# CPU_DDR2.net
KiCad netlist of a schematic drawn in Altium Designer
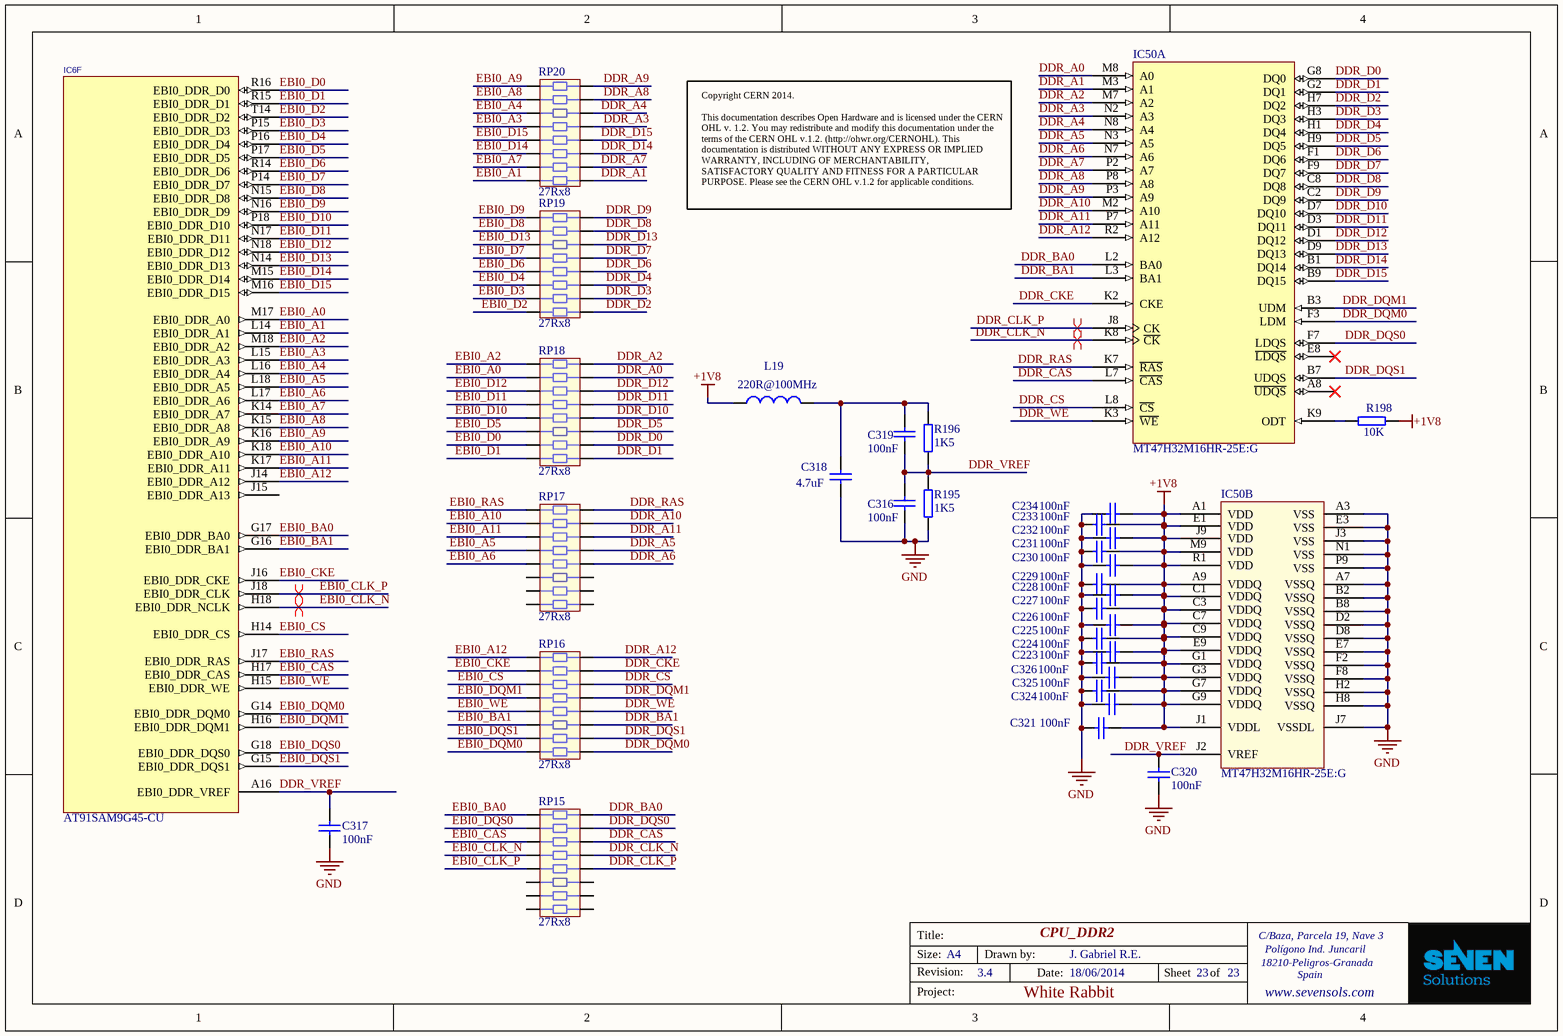
[diagram p0: CPU_DDR2.SchDoc]

(export (version "E")
  (design (tool "Eeschema 10.0.6"))
  (components
    (comp (ref "C223")
      (value "100nF")
      (footprint "CC1005-0402")
      (description "Capacitor")
      (fields
        (field (name "TOLERANCE") "±10%")
        (field (name "VOLTAGE") "16V")
        (field (name "PUBLISHER") "Altium Limited")
      )
      (libsource (lib "wr_switch") (part "Cap"))
    )
    (comp (ref "C224")
      (value "100nF")
      (footprint "CC1005-0402")
      (description "Capacitor")
      (fields
        (field (name "TOLERANCE") "±10%")
        (field (name "VOLTAGE") "16V")
        (field (name "PUBLISHER") "Altium Limited")
      )
      (libsource (lib "wr_switch") (part "Cap"))
    )
    (comp (ref "C225")
      (value "100nF")
      (footprint "CC1005-0402")
      (description "Capacitor")
      (fields
        (field (name "TOLERANCE") "±10%")
        (field (name "VOLTAGE") "16V")
        (field (name "PUBLISHER") "Altium Limited")
      )
      (libsource (lib "wr_switch") (part "Cap"))
    )
    (comp (ref "C226")
      (value "100nF")
      (footprint "CC1005-0402")
      (description "Capacitor")
      (fields
        (field (name "TOLERANCE") "±10%")
        (field (name "VOLTAGE") "16V")
        (field (name "PUBLISHER") "Altium Limited")
      )
      (libsource (lib "wr_switch") (part "Cap"))
    )
    (comp (ref "C227")
      (value "100nF")
      (footprint "CC1005-0402")
      (description "Capacitor")
      (fields
        (field (name "TOLERANCE") "±10%")
        (field (name "VOLTAGE") "16V")
        (field (name "PUBLISHER") "Altium Limited")
      )
      (libsource (lib "wr_switch") (part "Cap"))
    )
    (comp (ref "C228")
      (value "100nF")
      (footprint "CC1005-0402")
      (description "Capacitor")
      (fields
        (field (name "TOLERANCE") "±10%")
        (field (name "VOLTAGE") "16V")
        (field (name "PUBLISHER") "Altium Limited")
      )
      (libsource (lib "wr_switch") (part "Cap"))
    )
    (comp (ref "C229")
      (value "100nF")
      (footprint "CC1005-0402")
      (description "Capacitor")
      (fields
        (field (name "TOLERANCE") "±10%")
        (field (name "VOLTAGE") "16V")
        (field (name "PUBLISHER") "Altium Limited")
      )
      (libsource (lib "wr_switch") (part "Cap"))
    )
    (comp (ref "C230")
      (value "100nF")
      (footprint "CC1005-0402")
      (description "Capacitor")
      (fields
        (field (name "TOLERANCE") "±10%")
        (field (name "VOLTAGE") "16V")
        (field (name "PUBLISHER") "Altium Limited")
      )
      (libsource (lib "wr_switch") (part "Cap"))
    )
    (comp (ref "C231")
      (value "100nF")
      (footprint "CC1005-0402")
      (description "Capacitor")
      (fields
        (field (name "TOLERANCE") "±10%")
        (field (name "VOLTAGE") "16V")
        (field (name "PUBLISHER") "Altium Limited")
      )
      (libsource (lib "wr_switch") (part "Cap"))
    )
    (comp (ref "C232")
      (value "100nF")
      (footprint "CC1005-0402")
      (description "Capacitor")
      (fields
        (field (name "TOLERANCE") "±10%")
        (field (name "VOLTAGE") "16V")
        (field (name "PUBLISHER") "Altium Limited")
      )
      (libsource (lib "wr_switch") (part "Cap"))
    )
    (comp (ref "C233")
      (value "100nF")
      (footprint "CC1005-0402")
      (description "Capacitor")
      (fields
        (field (name "TOLERANCE") "±10%")
        (field (name "VOLTAGE") "16V")
        (field (name "PUBLISHER") "Altium Limited")
      )
      (libsource (lib "wr_switch") (part "Cap"))
    )
    (comp (ref "C234")
      (value "100nF")
      (footprint "CC1005-0402")
      (description "Capacitor")
      (fields
        (field (name "TOLERANCE") "±10%")
        (field (name "VOLTAGE") "16V")
        (field (name "PUBLISHER") "Altium Limited")
      )
      (libsource (lib "wr_switch") (part "Cap"))
    )
    (comp (ref "C316")
      (value "100nF")
      (footprint "CC1005-0402")
      (description "Capacitor")
      (fields
        (field (name "TOLERANCE") "±10%")
        (field (name "VOLTAGE") "16V")
        (field (name "PUBLISHER") "Altium Limited")
      )
      (libsource (lib "wr_switch") (part "Cap"))
    )
    (comp (ref "C317")
      (value "100nF")
      (footprint "CC1005-0402")
      (description "Capacitor")
      (fields
        (field (name "TOLERANCE") "±10%")
        (field (name "VOLTAGE") "16V")
        (field (name "PUBLISHER") "Altium Limited")
      )
      (libsource (lib "wr_switch") (part "Cap"))
    )
    (comp (ref "C318")
      (value "4.7uF")
      (footprint "CC1608-0603")
      (description "Capacitor")
      (fields
        (field (name "TOLERANCE") "±10%")
        (field (name "VOLTAGE") "10V")
        (field (name "PUBLISHER") "Altium Limited")
      )
      (libsource (lib "wr_switch") (part "Cap"))
    )
    (comp (ref "C319")
      (value "100nF")
      (footprint "CC1005-0402")
      (description "Capacitor")
      (fields
        (field (name "TOLERANCE") "±10%")
        (field (name "VOLTAGE") "16V")
        (field (name "PUBLISHER") "Altium Limited")
      )
      (libsource (lib "wr_switch") (part "Cap"))
    )
    (comp (ref "C320")
      (value "100nF")
      (footprint "CC1005-0402")
      (description "Capacitor")
      (fields
        (field (name "TOLERANCE") "±10%")
        (field (name "VOLTAGE") "16V")
        (field (name "PUBLISHER") "Altium Limited")
      )
      (libsource (lib "wr_switch") (part "Cap"))
    )
    (comp (ref "C321")
      (value "100nF")
      (footprint "CC1005-0402")
      (description "Capacitor")
      (fields
        (field (name "TOLERANCE") "±10%")
        (field (name "VOLTAGE") "16V")
        (field (name "PUBLISHER") "Altium Limited")
      )
      (libsource (lib "wr_switch") (part "Cap"))
    )
    (comp (ref "C324")
      (value "100nF")
      (footprint "CC1005-0402")
      (description "Capacitor")
      (fields
        (field (name "TOLERANCE") "±10%")
        (field (name "VOLTAGE") "16V")
        (field (name "PUBLISHER") "Altium Limited")
      )
      (libsource (lib "wr_switch") (part "Cap"))
    )
    (comp (ref "C325")
      (value "100nF")
      (footprint "CC1005-0402")
      (description "Capacitor")
      (fields
        (field (name "TOLERANCE") "±10%")
        (field (name "VOLTAGE") "16V")
        (field (name "PUBLISHER") "Altium Limited")
      )
      (libsource (lib "wr_switch") (part "Cap"))
    )
    (comp (ref "C326")
      (value "100nF")
      (footprint "CC1005-0402")
      (description "Capacitor")
      (fields
        (field (name "TOLERANCE") "±10%")
        (field (name "VOLTAGE") "16V")
        (field (name "PUBLISHER") "Altium Limited")
      )
      (libsource (lib "wr_switch") (part "Cap"))
    )
    (comp (ref "IC6")
      (value "AT91SAM9G45-CU")
      (footprint "TFBGA324")
      (description "Atmel 400MHz ARM926 MCU")
      (libsource (lib "wr_switch") (part "AT91SAM9G45-CU"))
    )
    (comp (ref "IC50")
      (value "MT47H32M16HR-25E:G")
      (footprint "7S_WR:BGA90C80P9X15_1250X800X120")
      (description "DDR2 SDRAM 8Mx16x4 Banks")
      (libsource (lib "wr_switch") (part "MT47H32M16"))
    )
    (comp (ref "L19")
      (value "220R@100MHz Ferrite Bead")
      (footprint "0603")
      (description "ferrite bead")
      (fields (field (name "IMPEDANCE") "220R@100MHz"))
      (libsource (lib "wr_switch") (part "L_FERRITE_BEAD"))
    )
    (comp (ref "R195")
      (value "1K5")
      (footprint "0402")
      (description "SMD Resistor")
      (fields (field (name "TOLERANCE") "±1%"))
      (libsource (lib "wr_switch") (part "RES_SMD"))
    )
    (comp (ref "R196")
      (value "1K5")
      (footprint "0402")
      (description "SMD Resistor")
      (fields (field (name "TOLERANCE") "±1%"))
      (libsource (lib "wr_switch") (part "RES_SMD"))
    )
    (comp (ref "R198")
      (value "10K")
      (footprint "0402")
      (description "SMD Resistor")
      (fields (field (name "TOLERANCE") "±1%"))
      (libsource (lib "wr_switch") (part "RES_SMD"))
    )
    (comp (ref "RP15")
      (value "27Rx8")
      (footprint "RESCAXS50P160X380X60-16N")
      (description "27R, 62.5mW Chip Resistor 8 Elements Array")
      (fields (field (name "TOLERANCE") "±5%") (field (name "Comment") "27R x 8"))
      (libsource (lib "") (part "RES_8xARRAY_1"))
    )
    (comp (ref "RP16")
      (value "27Rx8")
      (footprint "RESCAXS50P160X380X60-16N")
      (description "27R, 62.5mW Chip Resistor 8 Elements Array")
      (fields (field (name "TOLERANCE") "±5%") (field (name "Comment") "27R x 8"))
      (libsource (lib "") (part "RES_8xARRAY_1"))
    )
    (comp (ref "RP17")
      (value "27Rx8")
      (footprint "RESCAXS50P160X380X60-16N")
      (description "27R, 62.5mW Chip Resistor 8 Elements Array")
      (fields (field (name "TOLERANCE") "±5%") (field (name "Comment") "27R x 8"))
      (libsource (lib "") (part "RES_8xARRAY_1"))
    )
    (comp (ref "RP18")
      (value "27Rx8")
      (footprint "RESCAXS50P160X380X60-16N")
      (description "27R, 62.5mW Chip Resistor 8 Elements Array")
      (fields (field (name "TOLERANCE") "±5%") (field (name "Comment") "27R x 8"))
      (libsource (lib "") (part "RES_8xARRAY_1"))
    )
    (comp (ref "RP19")
      (value "27Rx8")
      (footprint "RESCAXS50P160X380X60-16N")
      (description "27R, 62.5mW Chip Resistor 8 Elements Array")
      (fields (field (name "TOLERANCE") "±5%") (field (name "Comment") "27R x 8"))
      (libsource (lib "wr_switch") (part "RES_8xARRAY"))
    )
    (comp (ref "RP20")
      (value "27Rx8")
      (footprint "RESCAXS50P160X380X60-16N")
      (description "27R, 62.5mW Chip Resistor 8 Elements Array")
      (fields (field (name "TOLERANCE") "±5%") (field (name "Comment") "27R x 8"))
      (libsource (lib "wr_switch") (part "RES_8xARRAY"))
    )
  )
  (nets
    (net (code "1") (name "+1V8") (class "Default")
      (node (ref "C223") (pin "1") (pinfunction "1_1") (pintype "passive"))
      (node (ref "C224") (pin "1") (pinfunction "1_1") (pintype "passive"))
      (node (ref "C225") (pin "1") (pinfunction "1_1") (pintype "passive"))
      (node (ref "C226") (pin "1") (pinfunction "1_1") (pintype "passive"))
      (node (ref "C227") (pin "1") (pinfunction "1_1") (pintype "passive"))
      (node (ref "C228") (pin "1") (pinfunction "1_1") (pintype "passive"))
      (node (ref "C229") (pin "1") (pinfunction "1_1") (pintype "passive"))
      (node (ref "C230") (pin "1") (pinfunction "1_1") (pintype "passive"))
      (node (ref "C231") (pin "1") (pinfunction "1_1") (pintype "passive"))
      (node (ref "C232") (pin "1") (pinfunction "1_1") (pintype "passive"))
      (node (ref "C233") (pin "1") (pinfunction "1_1") (pintype "passive"))
      (node (ref "C234") (pin "1") (pinfunction "1_1") (pintype "passive"))
      (node (ref "C321") (pin "1") (pinfunction "1_1") (pintype "passive"))
      (node (ref "C324") (pin "1") (pinfunction "1_1") (pintype "passive"))
      (node (ref "C325") (pin "1") (pinfunction "1_1") (pintype "passive"))
      (node (ref "C326") (pin "1") (pinfunction "1_1") (pintype "passive"))
      (node (ref "IC50") (pin "A1") (pinfunction "VDD_A1") (pintype "power_in"))
      (node (ref "IC50") (pin "A9") (pinfunction "VDDQ_A9") (pintype "power_in"))
      (node (ref "IC50") (pin "C1") (pinfunction "VDDQ_C1") (pintype "power_in"))
      (node (ref "IC50") (pin "C3") (pinfunction "VDDQ_C3") (pintype "power_in"))
      (node (ref "IC50") (pin "C7") (pinfunction "VDDQ_C7") (pintype "power_in"))
      (node (ref "IC50") (pin "C9") (pinfunction "VDDQ_C9") (pintype "power_in"))
      (node (ref "IC50") (pin "E1") (pinfunction "VDD_E1") (pintype "power_in"))
      (node (ref "IC50") (pin "E9") (pinfunction "VDDQ_E9") (pintype "power_in"))
      (node (ref "IC50") (pin "G1") (pinfunction "VDDQ_G1") (pintype "power_in"))
      (node (ref "IC50") (pin "G3") (pinfunction "VDDQ_G3") (pintype "power_in"))
      (node (ref "IC50") (pin "G7") (pinfunction "VDDQ_G7") (pintype "power_in"))
      (node (ref "IC50") (pin "G9") (pinfunction "VDDQ_G9") (pintype "power_in"))
      (node (ref "IC50") (pin "J1") (pinfunction "VDDL_J1") (pintype "power_in"))
      (node (ref "IC50") (pin "J9") (pinfunction "VDD_J9") (pintype "power_in"))
      (node (ref "IC50") (pin "M9") (pinfunction "VDD_M9") (pintype "power_in"))
      (node (ref "IC50") (pin "R1") (pinfunction "VDD_R1") (pintype "power_in"))
      (node (ref "L19") (pin "1") (pinfunction "1_1") (pintype "passive"))
      (node (ref "R198") (pin "1") (pinfunction "1_1") (pintype "passive"))
    )
    (net (code "2") (name "/DDR_A0") (class "Default")
      (node (ref "IC50") (pin "M8") (pinfunction "A0_M8") (pintype "input"))
      (node (ref "RP18") (pin "15") (pinfunction "15_15") (pintype "passive"))
    )
    (net (code "3") (name "/DDR_A1") (class "Default")
      (node (ref "IC50") (pin "M3") (pinfunction "A1_M3") (pintype "input"))
      (node (ref "RP20") (pin "16") (pinfunction "16_16") (pintype "passive"))
    )
    (net (code "4") (name "/DDR_A2") (class "Default")
      (node (ref "IC50") (pin "M7") (pinfunction "A2_M7") (pintype "input"))
      (node (ref "RP18") (pin "16") (pinfunction "16_16") (pintype "passive"))
    )
    (net (code "5") (name "/DDR_A3") (class "Default")
      (node (ref "IC50") (pin "N2") (pinfunction "A3_N2") (pintype "input"))
      (node (ref "RP20") (pin "12") (pinfunction "12_12") (pintype "passive"))
    )
    (net (code "6") (name "/DDR_A4") (class "Default")
      (node (ref "IC50") (pin "N8") (pinfunction "A4_N8") (pintype "input"))
      (node (ref "RP20") (pin "11") (pinfunction "11_11") (pintype "passive"))
    )
    (net (code "7") (name "/DDR_A5") (class "Default")
      (node (ref "IC50") (pin "N3") (pinfunction "A5_N3") (pintype "input"))
      (node (ref "RP17") (pin "13") (pinfunction "13_13") (pintype "passive"))
    )
    (net (code "8") (name "/DDR_A6") (class "Default")
      (node (ref "IC50") (pin "N7") (pinfunction "A6_N7") (pintype "input"))
      (node (ref "RP17") (pin "12") (pinfunction "12_12") (pintype "passive"))
    )
    (net (code "9") (name "/DDR_A7") (class "Default")
      (node (ref "IC50") (pin "P2") (pinfunction "A7_P2") (pintype "input"))
      (node (ref "RP20") (pin "15") (pinfunction "15_15") (pintype "passive"))
    )
    (net (code "10") (name "/DDR_A8") (class "Default")
      (node (ref "IC50") (pin "P8") (pinfunction "A8_P8") (pintype "input"))
      (node (ref "RP20") (pin "10") (pinfunction "10_10") (pintype "passive"))
    )
    (net (code "11") (name "/DDR_A9") (class "Default")
      (node (ref "IC50") (pin "P3") (pinfunction "A9_P3") (pintype "input"))
      (node (ref "RP20") (pin "9") (pinfunction "9_9") (pintype "passive"))
    )
    (net (code "12") (name "/DDR_A10") (class "Default")
      (node (ref "IC50") (pin "M2") (pinfunction "A10_M2") (pintype "input"))
      (node (ref "RP17") (pin "15") (pinfunction "15_15") (pintype "passive"))
    )
    (net (code "13") (name "/DDR_A11") (class "Default")
      (node (ref "IC50") (pin "P7") (pinfunction "A11_P7") (pintype "input"))
      (node (ref "RP17") (pin "14") (pinfunction "14_14") (pintype "passive"))
    )
    (net (code "14") (name "/DDR_A12") (class "Default")
      (node (ref "IC50") (pin "R2") (pinfunction "A12_R2") (pintype "input"))
      (node (ref "RP16") (pin "16") (pinfunction "16_16") (pintype "passive"))
    )
    (net (code "15") (name "/DDR_BA0") (class "Default")
      (node (ref "IC50") (pin "L2") (pinfunction "BA0_L2") (pintype "input"))
      (node (ref "RP15") (pin "16") (pinfunction "16_16") (pintype "passive"))
    )
    (net (code "16") (name "/DDR_BA1") (class "Default")
      (node (ref "IC50") (pin "L3") (pinfunction "BA1_L3") (pintype "input"))
      (node (ref "RP16") (pin "11") (pinfunction "11_11") (pintype "passive"))
    )
    (net (code "17") (name "/DDR_CAS") (class "Default")
      (node (ref "IC50") (pin "L7") (pinfunction "~{CAS}_L7") (pintype "input"))
      (node (ref "RP15") (pin "14") (pinfunction "14_14") (pintype "passive"))
    )
    (net (code "18") (name "/DDR_CKE") (class "Default")
      (node (ref "IC50") (pin "K2") (pinfunction "CKE_K2") (pintype "input"))
      (node (ref "RP16") (pin "15") (pinfunction "15_15") (pintype "passive"))
    )
    (net (code "19") (name "/DDR_CLK_N") (class "Default")
      (node (ref "IC50") (pin "K8") (pinfunction "~{CK}_K8") (pintype "input"))
      (node (ref "RP15") (pin "13") (pinfunction "13_13") (pintype "passive"))
    )
    (net (code "20") (name "/DDR_CLK_P") (class "Default")
      (node (ref "IC50") (pin "J8") (pinfunction "CK_J8") (pintype "input"))
      (node (ref "RP15") (pin "12") (pinfunction "12_12") (pintype "passive"))
    )
    (net (code "21") (name "/DDR_CS") (class "Default")
      (node (ref "IC50") (pin "L8") (pinfunction "~{CS}_L8") (pintype "input"))
      (node (ref "RP16") (pin "14") (pinfunction "14_14") (pintype "passive"))
    )
    (net (code "22") (name "/DDR_D0") (class "Default")
      (node (ref "IC50") (pin "G8") (pinfunction "DQ0_G8") (pintype "bidirectional"))
      (node (ref "RP18") (pin "10") (pinfunction "10_10") (pintype "passive"))
    )
    (net (code "23") (name "/DDR_D1") (class "Default")
      (node (ref "IC50") (pin "G2") (pinfunction "DQ1_G2") (pintype "bidirectional"))
      (node (ref "RP18") (pin "9") (pinfunction "9_9") (pintype "passive"))
    )
    (net (code "24") (name "/DDR_D2") (class "Default")
      (node (ref "IC50") (pin "H7") (pinfunction "DQ2_H7") (pintype "bidirectional"))
      (node (ref "RP19") (pin "16") (pinfunction "16_16") (pintype "passive"))
    )
    (net (code "25") (name "/DDR_D3") (class "Default")
      (node (ref "IC50") (pin "H3") (pinfunction "DQ3_H3") (pintype "bidirectional"))
      (node (ref "RP19") (pin "15") (pinfunction "15_15") (pintype "passive"))
    )
    (net (code "26") (name "/DDR_D4") (class "Default")
      (node (ref "IC50") (pin "H1") (pinfunction "DQ4_H1") (pintype "bidirectional"))
      (node (ref "RP19") (pin "14") (pinfunction "14_14") (pintype "passive"))
    )
    (net (code "27") (name "/DDR_D5") (class "Default")
      (node (ref "IC50") (pin "H9") (pinfunction "DQ5_H9") (pintype "bidirectional"))
      (node (ref "RP18") (pin "11") (pinfunction "11_11") (pintype "passive"))
    )
    (net (code "28") (name "/DDR_D6") (class "Default")
      (node (ref "IC50") (pin "F1") (pinfunction "DQ6_F1") (pintype "bidirectional"))
      (node (ref "RP19") (pin "13") (pinfunction "13_13") (pintype "passive"))
    )
    (net (code "29") (name "/DDR_D7") (class "Default")
      (node (ref "IC50") (pin "F9") (pinfunction "DQ7_F9") (pintype "bidirectional"))
      (node (ref "RP19") (pin "12") (pinfunction "12_12") (pintype "passive"))
    )
    (net (code "30") (name "/DDR_D8") (class "Default")
      (node (ref "IC50") (pin "C8") (pinfunction "DQ8_C8") (pintype "bidirectional"))
      (node (ref "RP19") (pin "10") (pinfunction "10_10") (pintype "passive"))
    )
    (net (code "31") (name "/DDR_D9") (class "Default")
      (node (ref "IC50") (pin "C2") (pinfunction "DQ9_C2") (pintype "bidirectional"))
      (node (ref "RP19") (pin "9") (pinfunction "9_9") (pintype "passive"))
    )
    (net (code "32") (name "/DDR_D10") (class "Default")
      (node (ref "IC50") (pin "D7") (pinfunction "DQ10_D7") (pintype "bidirectional"))
      (node (ref "RP18") (pin "12") (pinfunction "12_12") (pintype "passive"))
    )
    (net (code "33") (name "/DDR_D11") (class "Default")
      (node (ref "IC50") (pin "D3") (pinfunction "DQ11_D3") (pintype "bidirectional"))
      (node (ref "RP18") (pin "13") (pinfunction "13_13") (pintype "passive"))
    )
    (net (code "34") (name "/DDR_D12") (class "Default")
      (node (ref "IC50") (pin "D1") (pinfunction "DQ12_D1") (pintype "bidirectional"))
      (node (ref "RP18") (pin "14") (pinfunction "14_14") (pintype "passive"))
    )
    (net (code "35") (name "/DDR_D13") (class "Default")
      (node (ref "IC50") (pin "D9") (pinfunction "DQ13_D9") (pintype "bidirectional"))
      (node (ref "RP19") (pin "11") (pinfunction "11_11") (pintype "passive"))
    )
    (net (code "36") (name "/DDR_D14") (class "Default")
      (node (ref "IC50") (pin "B1") (pinfunction "DQ14_B1") (pintype "bidirectional"))
      (node (ref "RP20") (pin "14") (pinfunction "14_14") (pintype "passive"))
    )
    (net (code "37") (name "/DDR_D15") (class "Default")
      (node (ref "IC50") (pin "B9") (pinfunction "DQ15_B9") (pintype "bidirectional"))
      (node (ref "RP20") (pin "13") (pinfunction "13_13") (pintype "passive"))
    )
    (net (code "38") (name "/DDR_DQM0") (class "Default")
      (node (ref "IC50") (pin "F3") (pinfunction "LDM_F3") (pintype "input"))
      (node (ref "RP16") (pin "9") (pinfunction "9_9") (pintype "passive"))
    )
    (net (code "39") (name "/DDR_DQM1") (class "Default")
      (node (ref "IC50") (pin "B3") (pinfunction "UDM_B3") (pintype "input"))
      (node (ref "RP16") (pin "13") (pinfunction "13_13") (pintype "passive"))
    )
    (net (code "40") (name "/DDR_DQS0") (class "Default")
      (node (ref "IC50") (pin "F7") (pinfunction "LDQS_F7") (pintype "bidirectional"))
      (node (ref "RP15") (pin "15") (pinfunction "15_15") (pintype "passive"))
    )
    (net (code "41") (name "/DDR_DQS1") (class "Default")
      (node (ref "IC50") (pin "B7") (pinfunction "UDQS_B7") (pintype "bidirectional"))
      (node (ref "RP16") (pin "10") (pinfunction "10_10") (pintype "passive"))
    )
    (net (code "42") (name "/DDR_RAS") (class "Default")
      (node (ref "IC50") (pin "K7") (pinfunction "~{RAS}_K7") (pintype "input"))
      (node (ref "RP17") (pin "16") (pinfunction "16_16") (pintype "passive"))
    )
    (net (code "43") (name "/DDR_VREF") (class "Default")
      (node (ref "C316") (pin "1") (pinfunction "1_1") (pintype "passive"))
      (node (ref "C317") (pin "1") (pinfunction "1_1") (pintype "passive"))
      (node (ref "C319") (pin "2") (pinfunction "2_2") (pintype "passive"))
      (node (ref "C320") (pin "1") (pinfunction "1_1") (pintype "passive"))
      (node (ref "IC50") (pin "J2") (pinfunction "VREF_J2") (pintype "power_in"))
      (node (ref "IC6") (pin "A16") (pinfunction "EBI0_DDR_VREF_A16") (pintype "passive"))
      (node (ref "R195") (pin "2") (pinfunction "2_2") (pintype "passive"))
      (node (ref "R196") (pin "1") (pinfunction "1_1") (pintype "passive"))
    )
    (net (code "44") (name "/DDR_WE") (class "Default")
      (node (ref "IC50") (pin "K3") (pinfunction "~{WE}_K3") (pintype "input"))
      (node (ref "RP16") (pin "12") (pinfunction "12_12") (pintype "passive"))
    )
    (net (code "45") (name "/EBI0_A0") (class "Default")
      (node (ref "IC6") (pin "M17") (pinfunction "EBI0_DDR_A0_M17") (pintype "output"))
      (node (ref "RP18") (pin "2") (pinfunction "2_2") (pintype "passive"))
    )
    (net (code "46") (name "/EBI0_A1") (class "Default")
      (node (ref "IC6") (pin "L14") (pinfunction "EBI0_DDR_A1_L14") (pintype "output"))
      (node (ref "RP20") (pin "1") (pinfunction "1_1") (pintype "passive"))
    )
    (net (code "47") (name "/EBI0_A2") (class "Default")
      (node (ref "IC6") (pin "M18") (pinfunction "EBI0_DDR_A2_M18") (pintype "output"))
      (node (ref "RP18") (pin "1") (pinfunction "1_1") (pintype "passive"))
    )
    (net (code "48") (name "/EBI0_A3") (class "Default")
      (node (ref "IC6") (pin "L15") (pinfunction "EBI0_DDR_A3_L15") (pintype "output"))
      (node (ref "RP20") (pin "5") (pinfunction "5_5") (pintype "passive"))
    )
    (net (code "49") (name "/EBI0_A4") (class "Default")
      (node (ref "IC6") (pin "L16") (pinfunction "EBI0_DDR_A4_L16") (pintype "output"))
      (node (ref "RP20") (pin "6") (pinfunction "6_6") (pintype "passive"))
    )
    (net (code "50") (name "/EBI0_A5") (class "Default")
      (node (ref "IC6") (pin "L18") (pinfunction "EBI0_DDR_A5_L18") (pintype "output"))
      (node (ref "RP17") (pin "4") (pinfunction "4_4") (pintype "passive"))
    )
    (net (code "51") (name "/EBI0_A6") (class "Default")
      (node (ref "IC6") (pin "L17") (pinfunction "EBI0_DDR_A6_L17") (pintype "output"))
      (node (ref "RP17") (pin "5") (pinfunction "5_5") (pintype "passive"))
    )
    (net (code "52") (name "/EBI0_A7") (class "Default")
      (node (ref "IC6") (pin "K14") (pinfunction "EBI0_DDR_A7_K14") (pintype "output"))
      (node (ref "RP20") (pin "2") (pinfunction "2_2") (pintype "passive"))
    )
    (net (code "53") (name "/EBI0_A8") (class "Default")
      (node (ref "IC6") (pin "K15") (pinfunction "EBI0_DDR_A8_K15") (pintype "output"))
      (node (ref "RP20") (pin "7") (pinfunction "7_7") (pintype "passive"))
    )
    (net (code "54") (name "/EBI0_A9") (class "Default")
      (node (ref "IC6") (pin "K16") (pinfunction "EBI0_DDR_A9_K16") (pintype "output"))
      (node (ref "RP20") (pin "8") (pinfunction "8_8") (pintype "passive"))
    )
    (net (code "55") (name "/EBI0_A10") (class "Default")
      (node (ref "IC6") (pin "K18") (pinfunction "EBI0_DDR_A10_K18") (pintype "output"))
      (node (ref "RP17") (pin "2") (pinfunction "2_2") (pintype "passive"))
    )
    (net (code "56") (name "/EBI0_A11") (class "Default")
      (node (ref "IC6") (pin "K17") (pinfunction "EBI0_DDR_A11_K17") (pintype "output"))
      (node (ref "RP17") (pin "3") (pinfunction "3_3") (pintype "passive"))
    )
    (net (code "57") (name "/EBI0_A12") (class "Default")
      (node (ref "IC6") (pin "J14") (pinfunction "EBI0_DDR_A12_J14") (pintype "output"))
      (node (ref "RP16") (pin "1") (pinfunction "1_1") (pintype "passive"))
    )
    (net (code "58") (name "/EBI0_BA0") (class "Default")
      (node (ref "IC6") (pin "G17") (pinfunction "EBI0_DDR_BA0_G17") (pintype "output"))
      (node (ref "RP15") (pin "1") (pinfunction "1_1") (pintype "passive"))
    )
    (net (code "59") (name "/EBI0_BA1") (class "Default")
      (node (ref "IC6") (pin "G16") (pinfunction "EBI0_DDR_BA1_G16") (pintype "output"))
      (node (ref "RP16") (pin "6") (pinfunction "6_6") (pintype "passive"))
    )
    (net (code "60") (name "/EBI0_CAS") (class "Default")
      (node (ref "IC6") (pin "H17") (pinfunction "EBI0_DDR_CAS_H17") (pintype "output"))
      (node (ref "RP15") (pin "3") (pinfunction "3_3") (pintype "passive"))
    )
    (net (code "61") (name "/EBI0_CKE") (class "Default")
      (node (ref "IC6") (pin "J16") (pinfunction "EBI0_DDR_CKE_J16") (pintype "output"))
      (node (ref "RP16") (pin "2") (pinfunction "2_2") (pintype "passive"))
    )
    (net (code "62") (name "/EBI0_CLK_N") (class "Default")
      (node (ref "IC6") (pin "H18") (pinfunction "EBI0_DDR_NCLK_H18") (pintype "output"))
      (node (ref "RP15") (pin "4") (pinfunction "4_4") (pintype "passive"))
    )
    (net (code "63") (name "/EBI0_CLK_P") (class "Default")
      (node (ref "IC6") (pin "J18") (pinfunction "EBI0_DDR_CLK_J18") (pintype "output"))
      (node (ref "RP15") (pin "5") (pinfunction "5_5") (pintype "passive"))
    )
    (net (code "64") (name "/EBI0_CS") (class "Default")
      (node (ref "IC6") (pin "H14") (pinfunction "EBI0_DDR_CS_H14") (pintype "output"))
      (node (ref "RP16") (pin "3") (pinfunction "3_3") (pintype "passive"))
    )
    (net (code "65") (name "/EBI0_D0") (class "Default")
      (node (ref "IC6") (pin "R16") (pinfunction "EBI0_DDR_D0_R16") (pintype "bidirectional"))
      (node (ref "RP18") (pin "7") (pinfunction "7_7") (pintype "passive"))
    )
    (net (code "66") (name "/EBI0_D1") (class "Default")
      (node (ref "IC6") (pin "R15") (pinfunction "EBI0_DDR_D1_R15") (pintype "bidirectional"))
      (node (ref "RP18") (pin "8") (pinfunction "8_8") (pintype "passive"))
    )
    (net (code "67") (name "/EBI0_D2") (class "Default")
      (node (ref "IC6") (pin "T14") (pinfunction "EBI0_DDR_D2_T14") (pintype "bidirectional"))
      (node (ref "RP19") (pin "1") (pinfunction "1_1") (pintype "passive"))
    )
    (net (code "68") (name "/EBI0_D3") (class "Default")
      (node (ref "IC6") (pin "P15") (pinfunction "EBI0_DDR_D3_P15") (pintype "bidirectional"))
      (node (ref "RP19") (pin "2") (pinfunction "2_2") (pintype "passive"))
    )
    (net (code "69") (name "/EBI0_D4") (class "Default")
      (node (ref "IC6") (pin "P16") (pinfunction "EBI0_DDR_D4_P16") (pintype "bidirectional"))
      (node (ref "RP19") (pin "3") (pinfunction "3_3") (pintype "passive"))
    )
    (net (code "70") (name "/EBI0_D5") (class "Default")
      (node (ref "IC6") (pin "P17") (pinfunction "EBI0_DDR_D5_P17") (pintype "bidirectional"))
      (node (ref "RP18") (pin "6") (pinfunction "6_6") (pintype "passive"))
    )
    (net (code "71") (name "/EBI0_D6") (class "Default")
      (node (ref "IC6") (pin "R14") (pinfunction "EBI0_DDR_D6_R14") (pintype "bidirectional"))
      (node (ref "RP19") (pin "4") (pinfunction "4_4") (pintype "passive"))
    )
    (net (code "72") (name "/EBI0_D7") (class "Default")
      (node (ref "IC6") (pin "P14") (pinfunction "EBI0_DDR_D7_P14") (pintype "bidirectional"))
      (node (ref "RP19") (pin "5") (pinfunction "5_5") (pintype "passive"))
    )
    (net (code "73") (name "/EBI0_D8") (class "Default")
      (node (ref "IC6") (pin "N15") (pinfunction "EBI0_DDR_D8_N15") (pintype "bidirectional"))
      (node (ref "RP19") (pin "7") (pinfunction "7_7") (pintype "passive"))
    )
    (net (code "74") (name "/EBI0_D9") (class "Default")
      (node (ref "IC6") (pin "N16") (pinfunction "EBI0_DDR_D9_N16") (pintype "bidirectional"))
      (node (ref "RP19") (pin "8") (pinfunction "8_8") (pintype "passive"))
    )
    (net (code "75") (name "/EBI0_D10") (class "Default")
      (node (ref "IC6") (pin "P18") (pinfunction "EBI0_DDR_D10_P18") (pintype "bidirectional"))
      (node (ref "RP18") (pin "5") (pinfunction "5_5") (pintype "passive"))
    )
    (net (code "76") (name "/EBI0_D11") (class "Default")
      (node (ref "IC6") (pin "N17") (pinfunction "EBI0_DDR_D11_N17") (pintype "bidirectional"))
      (node (ref "RP18") (pin "4") (pinfunction "4_4") (pintype "passive"))
    )
    (net (code "77") (name "/EBI0_D12") (class "Default")
      (node (ref "IC6") (pin "N18") (pinfunction "EBI0_DDR_D12_N18") (pintype "bidirectional"))
      (node (ref "RP18") (pin "3") (pinfunction "3_3") (pintype "passive"))
    )
    (net (code "78") (name "/EBI0_D13") (class "Default")
      (node (ref "IC6") (pin "N14") (pinfunction "EBI0_DDR_D13_N14") (pintype "bidirectional"))
      (node (ref "RP19") (pin "6") (pinfunction "6_6") (pintype "passive"))
    )
    (net (code "79") (name "/EBI0_D14") (class "Default")
      (node (ref "IC6") (pin "M15") (pinfunction "EBI0_DDR_D14_M15") (pintype "bidirectional"))
      (node (ref "RP20") (pin "3") (pinfunction "3_3") (pintype "passive"))
    )
    (net (code "80") (name "/EBI0_D15") (class "Default")
      (node (ref "IC6") (pin "M16") (pinfunction "EBI0_DDR_D15_M16") (pintype "bidirectional"))
      (node (ref "RP20") (pin "4") (pinfunction "4_4") (pintype "passive"))
    )
    (net (code "81") (name "/EBI0_DQM0") (class "Default")
      (node (ref "IC6") (pin "G14") (pinfunction "EBI0_DDR_DQM0_G14") (pintype "output"))
      (node (ref "RP16") (pin "8") (pinfunction "8_8") (pintype "passive"))
    )
    (net (code "82") (name "/EBI0_DQM1") (class "Default")
      (node (ref "IC6") (pin "H16") (pinfunction "EBI0_DDR_DQM1_H16") (pintype "output"))
      (node (ref "RP16") (pin "4") (pinfunction "4_4") (pintype "passive"))
    )
    (net (code "83") (name "/EBI0_DQS0") (class "Default")
      (node (ref "IC6") (pin "G18") (pinfunction "EBI0_DDR_DQS0_G18") (pintype "output"))
      (node (ref "RP15") (pin "2") (pinfunction "2_2") (pintype "passive"))
    )
    (net (code "84") (name "/EBI0_DQS1") (class "Default")
      (node (ref "IC6") (pin "G15") (pinfunction "EBI0_DDR_DQS1_G15") (pintype "output"))
      (node (ref "RP16") (pin "7") (pinfunction "7_7") (pintype "passive"))
    )
    (net (code "85") (name "/EBI0_RAS") (class "Default")
      (node (ref "IC6") (pin "J17") (pinfunction "EBI0_DDR_RAS_J17") (pintype "output"))
      (node (ref "RP17") (pin "1") (pinfunction "1_1") (pintype "passive"))
    )
    (net (code "86") (name "/EBI0_WE") (class "Default")
      (node (ref "IC6") (pin "H15") (pinfunction "EBI0_DDR_WE_H15") (pintype "output"))
      (node (ref "RP16") (pin "5") (pinfunction "5_5") (pintype "passive"))
    )
    (net (code "87") (name "GND") (class "Default")
      (node (ref "C223") (pin "2") (pinfunction "2_2") (pintype "passive"))
      (node (ref "C224") (pin "2") (pinfunction "2_2") (pintype "passive"))
      (node (ref "C225") (pin "2") (pinfunction "2_2") (pintype "passive"))
      (node (ref "C226") (pin "2") (pinfunction "2_2") (pintype "passive"))
      (node (ref "C227") (pin "2") (pinfunction "2_2") (pintype "passive"))
      (node (ref "C228") (pin "2") (pinfunction "2_2") (pintype "passive"))
      (node (ref "C229") (pin "2") (pinfunction "2_2") (pintype "passive"))
      (node (ref "C230") (pin "2") (pinfunction "2_2") (pintype "passive"))
      (node (ref "C231") (pin "2") (pinfunction "2_2") (pintype "passive"))
      (node (ref "C232") (pin "2") (pinfunction "2_2") (pintype "passive"))
      (node (ref "C233") (pin "2") (pinfunction "2_2") (pintype "passive"))
      (node (ref "C234") (pin "2") (pinfunction "2_2") (pintype "passive"))
      (node (ref "C316") (pin "2") (pinfunction "2_2") (pintype "passive"))
      (node (ref "C317") (pin "2") (pinfunction "2_2") (pintype "passive"))
      (node (ref "C318") (pin "1") (pinfunction "1_1") (pintype "passive"))
      (node (ref "C320") (pin "2") (pinfunction "2_2") (pintype "passive"))
      (node (ref "C321") (pin "2") (pinfunction "2_2") (pintype "passive"))
      (node (ref "C324") (pin "2") (pinfunction "2_2") (pintype "passive"))
      (node (ref "C325") (pin "2") (pinfunction "2_2") (pintype "passive"))
      (node (ref "C326") (pin "2") (pinfunction "2_2") (pintype "passive"))
      (node (ref "IC50") (pin "A3") (pinfunction "VSS_A3") (pintype "power_in"))
      (node (ref "IC50") (pin "A7") (pinfunction "VSSQ_A7") (pintype "power_in"))
      (node (ref "IC50") (pin "B2") (pinfunction "VSSQ_B2") (pintype "power_in"))
      (node (ref "IC50") (pin "B8") (pinfunction "VSSQ_B8") (pintype "power_in"))
      (node (ref "IC50") (pin "D2") (pinfunction "VSSQ_D2") (pintype "power_in"))
      (node (ref "IC50") (pin "D8") (pinfunction "VSSQ_D8") (pintype "power_in"))
      (node (ref "IC50") (pin "E3") (pinfunction "VSS_E3") (pintype "power_in"))
      (node (ref "IC50") (pin "E7") (pinfunction "VSSQ_E7") (pintype "power_in"))
      (node (ref "IC50") (pin "F2") (pinfunction "VSSQ_F2") (pintype "power_in"))
      (node (ref "IC50") (pin "F8") (pinfunction "VSSQ_F8") (pintype "power_in"))
      (node (ref "IC50") (pin "H2") (pinfunction "VSSQ_H2") (pintype "power_in"))
      (node (ref "IC50") (pin "H8") (pinfunction "VSSQ_H8") (pintype "power_in"))
      (node (ref "IC50") (pin "J3") (pinfunction "VSS_J3") (pintype "power_in"))
      (node (ref "IC50") (pin "J7") (pinfunction "VSSDL_J7") (pintype "power_in"))
      (node (ref "IC50") (pin "N1") (pinfunction "VSS_N1") (pintype "power_in"))
      (node (ref "IC50") (pin "P9") (pinfunction "VSS_P9") (pintype "power_in"))
      (node (ref "R195") (pin "1") (pinfunction "1_1") (pintype "passive"))
    )
    (net (code "88") (name "Net-(C318-Pad2)") (class "Default")
      (node (ref "C318") (pin "2") (pinfunction "2_2") (pintype "passive"))
      (node (ref "C319") (pin "1") (pinfunction "1_1") (pintype "passive"))
      (node (ref "L19") (pin "2") (pinfunction "2_2") (pintype "passive"))
      (node (ref "R196") (pin "2") (pinfunction "2_2") (pintype "passive"))
    )
    (net (code "89") (name "Net-(IC50A-ODT)") (class "Default")
      (node (ref "IC50") (pin "K9") (pinfunction "ODT_K9") (pintype "input"))
      (node (ref "R198") (pin "2") (pinfunction "2_2") (pintype "passive"))
    )
    (net (code "90") (name "unconnected-(IC6F-EBI0_DDR_A13-PadJ15)") (class "Default")
      (node (ref "IC6") (pin "J15") (pinfunction "EBI0_DDR_A13_J15") (pintype "output"))
    )
    (net (code "91") (name "unconnected-(IC50A-~{LDQS}-PadE8)") (class "Default")
      (node (ref "IC50") (pin "E8") (pinfunction "~{LDQS}_E8") (pintype "bidirectional+no_connect"))
    )
    (net (code "92") (name "unconnected-(IC50A-~{UDQS}-PadA8)") (class "Default")
      (node (ref "IC50") (pin "A8") (pinfunction "~{UDQS}_A8") (pintype "bidirectional+no_connect"))
    )
    (net (code "93") (name "unconnected-(RP15-Pad6)") (class "Default")
      (node (ref "RP15") (pin "6") (pinfunction "6_6") (pintype "passive"))
    )
    (net (code "94") (name "unconnected-(RP15-Pad7)") (class "Default")
      (node (ref "RP15") (pin "7") (pinfunction "7_7") (pintype "passive"))
    )
    (net (code "95") (name "unconnected-(RP15-Pad8)") (class "Default")
      (node (ref "RP15") (pin "8") (pinfunction "8_8") (pintype "passive"))
    )
    (net (code "96") (name "unconnected-(RP15-Pad9)") (class "Default")
      (node (ref "RP15") (pin "9") (pinfunction "9_9") (pintype "passive"))
    )
    (net (code "97") (name "unconnected-(RP15-Pad10)") (class "Default")
      (node (ref "RP15") (pin "10") (pinfunction "10_10") (pintype "passive"))
    )
    (net (code "98") (name "unconnected-(RP15-Pad11)") (class "Default")
      (node (ref "RP15") (pin "11") (pinfunction "11_11") (pintype "passive"))
    )
    (net (code "99") (name "unconnected-(RP17-Pad6)") (class "Default")
      (node (ref "RP17") (pin "6") (pinfunction "6_6") (pintype "passive"))
    )
    (net (code "100") (name "unconnected-(RP17-Pad7)") (class "Default")
      (node (ref "RP17") (pin "7") (pinfunction "7_7") (pintype "passive"))
    )
    (net (code "101") (name "unconnected-(RP17-Pad8)") (class "Default")
      (node (ref "RP17") (pin "8") (pinfunction "8_8") (pintype "passive"))
    )
    (net (code "102") (name "unconnected-(RP17-Pad9)") (class "Default")
      (node (ref "RP17") (pin "9") (pinfunction "9_9") (pintype "passive"))
    )
    (net (code "103") (name "unconnected-(RP17-Pad10)") (class "Default")
      (node (ref "RP17") (pin "10") (pinfunction "10_10") (pintype "passive"))
    )
    (net (code "104") (name "unconnected-(RP17-Pad11)") (class "Default")
      (node (ref "RP17") (pin "11") (pinfunction "11_11") (pintype "passive"))
    )
  )
)
